# Sheet1.net
KiCad netlist of a schematic drawn in Altium Designer
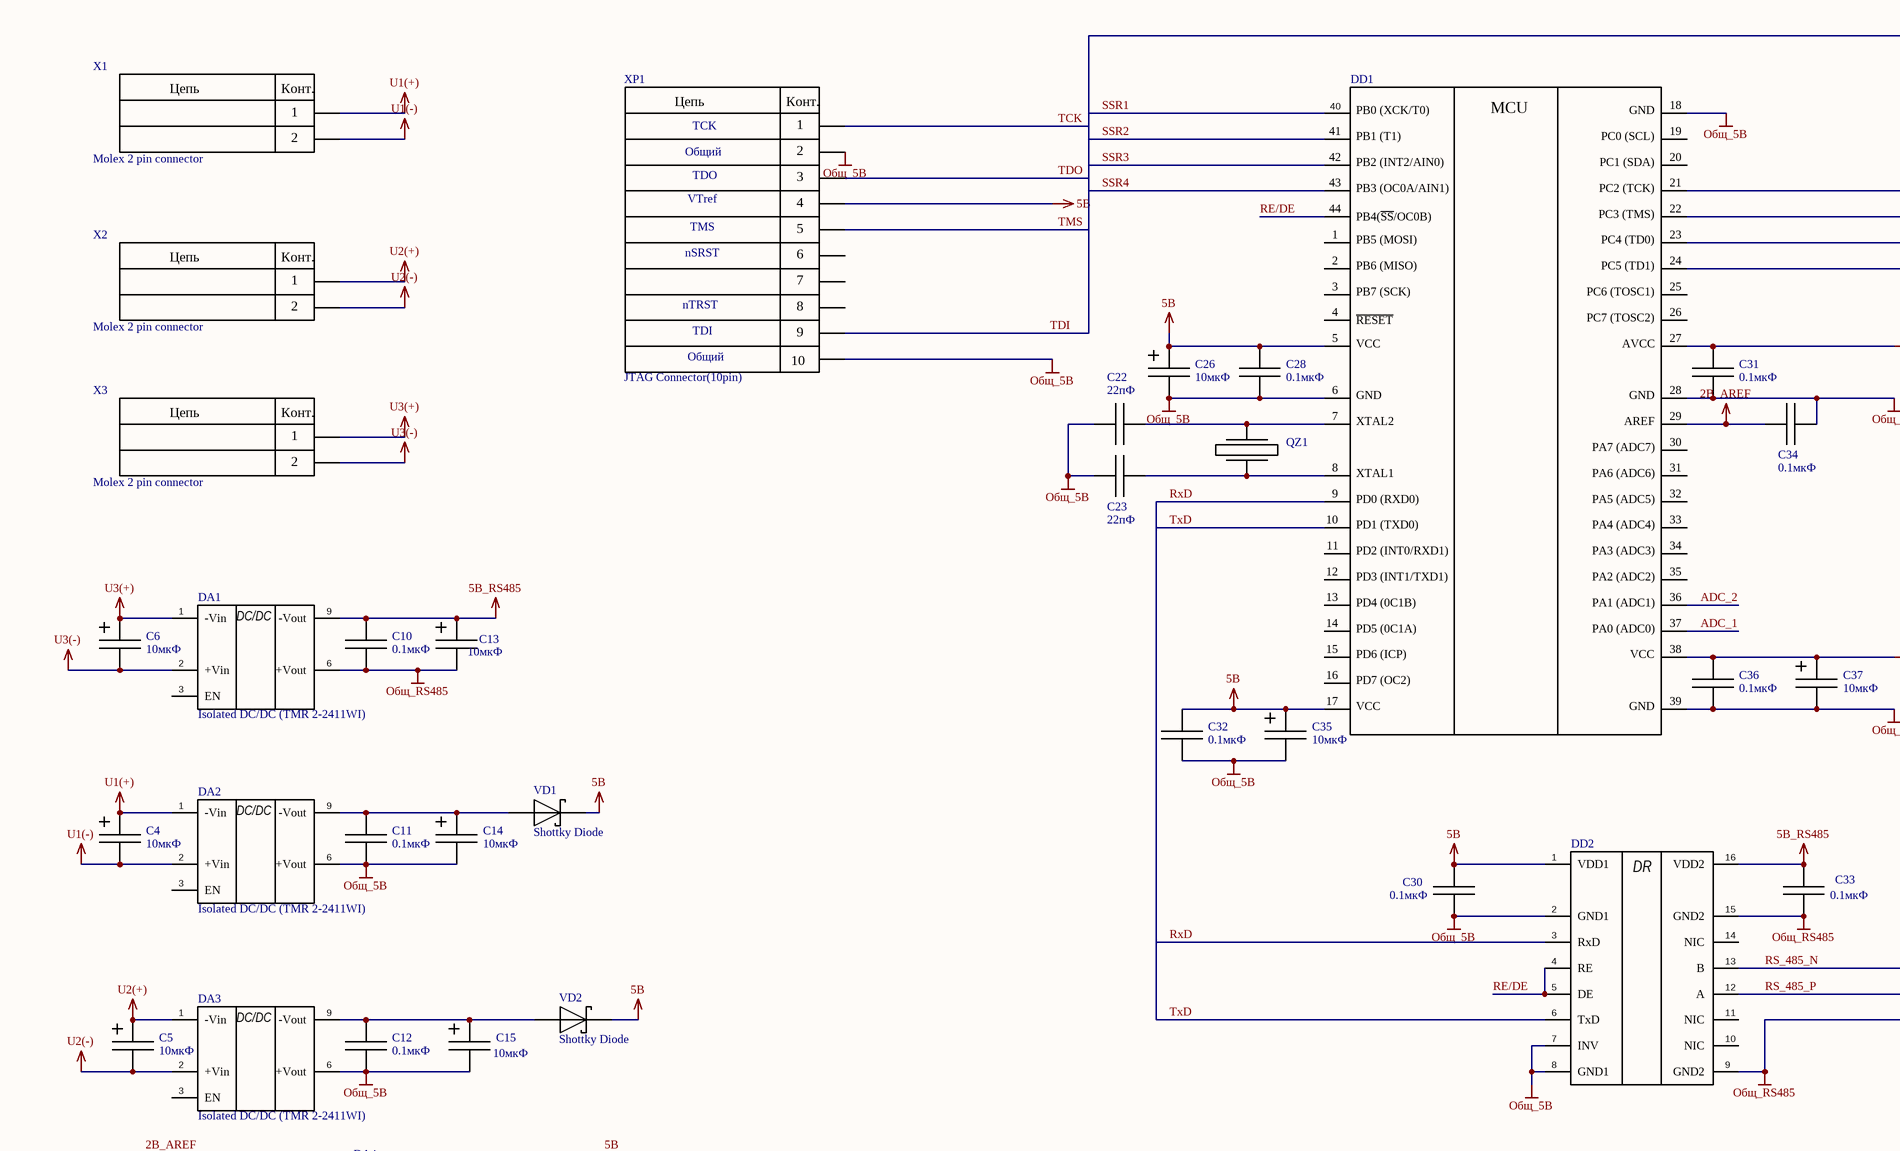
[diagram p0: Sheet1.SchDoc, top left]
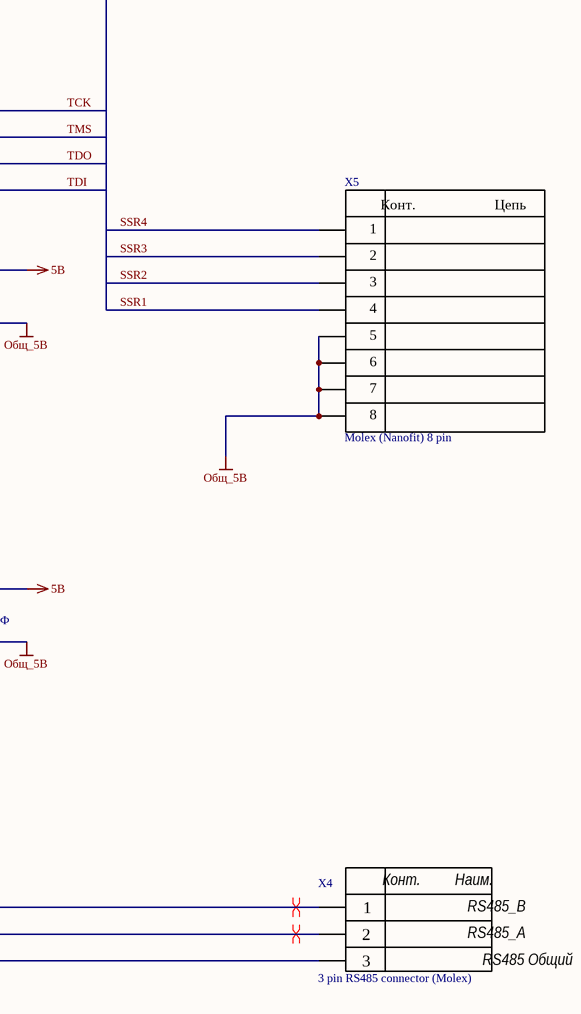
[diagram p1: Sheet1.SchDoc, top right]
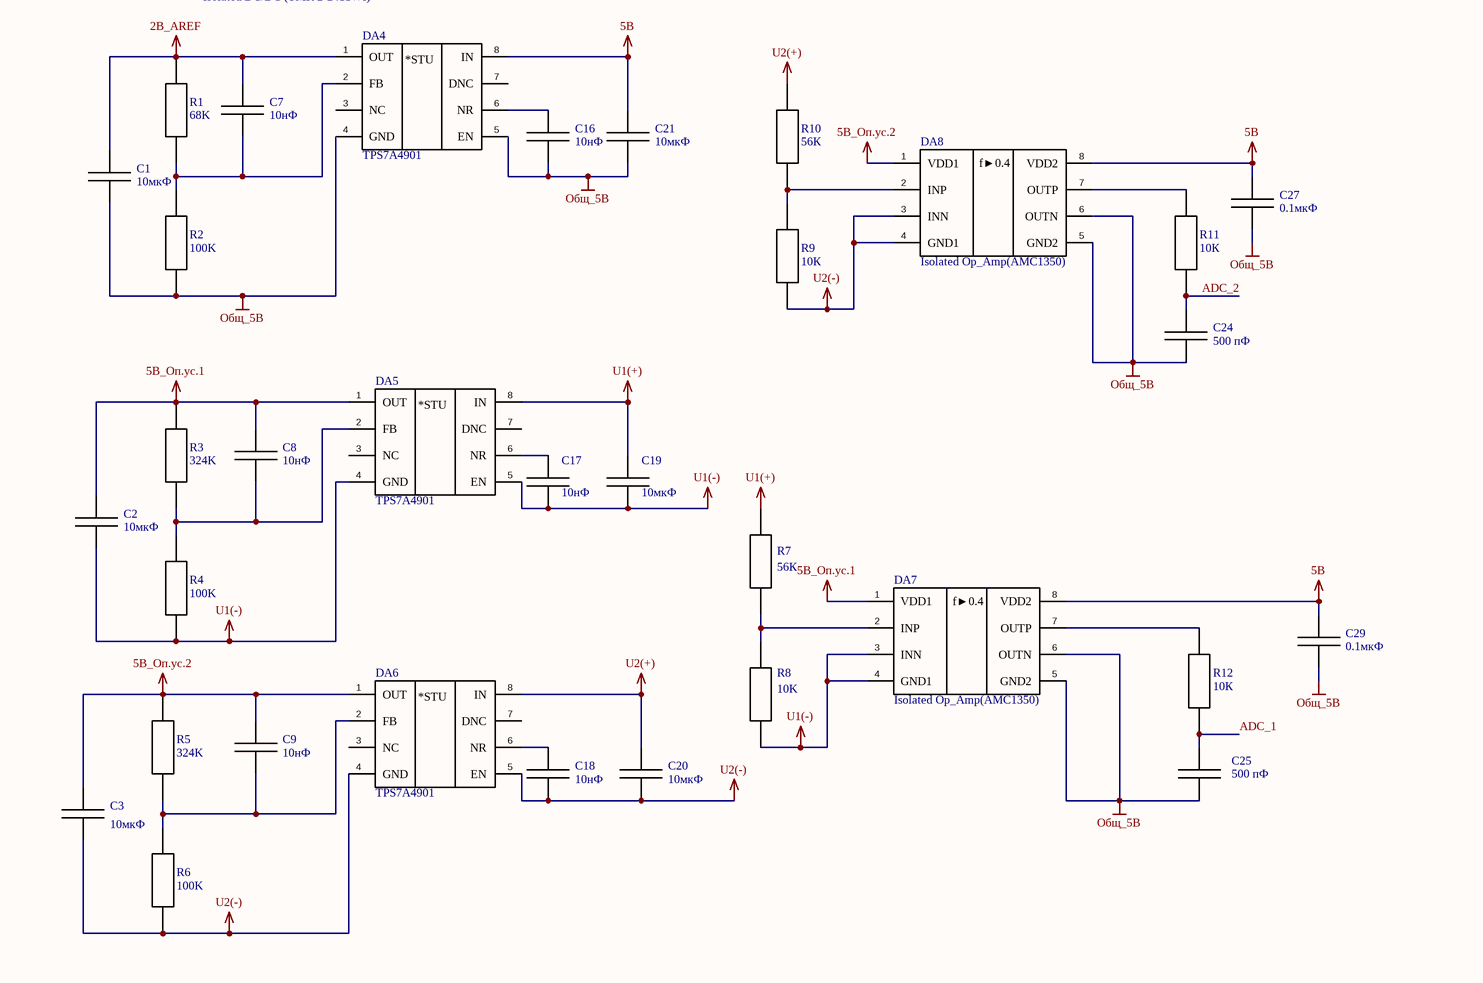
[diagram p2: Sheet1.SchDoc, bottom left]

(export (version "E")
  (design (tool "Eeschema 10.0.6"))
  (components
    (comp (ref "C1") (value "CAP") (footprint "0805") (libsource (lib "Kursovoi proekt") (part "CAP")))
    (comp (ref "C2") (value "CAP") (footprint "0805") (libsource (lib "Kursovoi proekt") (part "CAP")))
    (comp (ref "C3") (value "CAP") (footprint "0805") (libsource (lib "Kursovoi proekt") (part "CAP")))
    (comp (ref "C4")
      (value "CAP")
      (footprint "Cap pol 4x5.4")
      (description "ECAP SMD,  16VV, 105°C")
      (libsource (lib "Kursovoi proekt") (part "Cap Pol 10uF 16V"))
    )
    (comp (ref "C5")
      (value "CAP")
      (footprint "Cap pol 4x5.4")
      (description "ECAP SMD,  16VV, 105°C")
      (libsource (lib "Kursovoi proekt") (part "Cap Pol 10uF 16V"))
    )
    (comp (ref "C6")
      (value "CAP")
      (footprint "Cap pol 4x5.4")
      (description "ECAP SMD,  16VV, 105°C")
      (libsource (lib "Kursovoi proekt") (part "Cap Pol 10uF 16V"))
    )
    (comp (ref "C7") (value "CAP") (footprint "0805") (libsource (lib "Kursovoi proekt") (part "CAP")))
    (comp (ref "C8") (value "CAP") (footprint "0805") (libsource (lib "Kursovoi proekt") (part "CAP")))
    (comp (ref "C9") (value "CAP") (footprint "0805") (libsource (lib "Kursovoi proekt") (part "CAP")))
    (comp (ref "C10") (value "CAP") (footprint "0805") (libsource (lib "Kursovoi proekt") (part "CAP")))
    (comp (ref "C11") (value "CAP") (footprint "0805") (libsource (lib "Kursovoi proekt") (part "CAP")))
    (comp (ref "C12") (value "CAP") (footprint "0805") (libsource (lib "Kursovoi proekt") (part "CAP")))
    (comp (ref "C13")
      (value "CAP")
      (footprint "Cap pol 4x5.4")
      (description "ECAP SMD,  16VV, 105°C")
      (libsource (lib "Kursovoi proekt") (part "Cap Pol 10uF 16V"))
    )
    (comp (ref "C14")
      (value "CAP")
      (footprint "Cap pol 4x5.4")
      (description "ECAP SMD,  16VV, 105°C")
      (libsource (lib "Kursovoi proekt") (part "Cap Pol 10uF 16V"))
    )
    (comp (ref "C15")
      (value "CAP")
      (footprint "Cap pol 4x5.4")
      (description "ECAP SMD,  16VV, 105°C")
      (libsource (lib "Kursovoi proekt") (part "Cap Pol 10uF 16V"))
    )
    (comp (ref "C16") (value "CAP") (footprint "0805") (libsource (lib "Kursovoi proekt") (part "CAP")))
    (comp (ref "C17") (value "CAP") (footprint "0805") (libsource (lib "Kursovoi proekt") (part "CAP")))
    (comp (ref "C18") (value "CAP") (footprint "0805") (libsource (lib "Kursovoi proekt") (part "CAP")))
    (comp (ref "C19") (value "CAP") (footprint "0805") (libsource (lib "Kursovoi proekt") (part "CAP")))
    (comp (ref "C20") (value "CAP") (footprint "0805") (libsource (lib "Kursovoi proekt") (part "CAP")))
    (comp (ref "C21") (value "CAP") (footprint "0805") (libsource (lib "Kursovoi proekt") (part "CAP")))
    (comp (ref "C22") (value "CAP") (footprint "0805") (libsource (lib "Kursovoi proekt") (part "CAP")))
    (comp (ref "C23") (value "CAP") (footprint "0805") (libsource (lib "Kursovoi proekt") (part "CAP")))
    (comp (ref "C24") (value "CAP") (footprint "0805") (libsource (lib "Kursovoi proekt") (part "CAP")))
    (comp (ref "C25") (value "CAP") (footprint "0805") (libsource (lib "Kursovoi proekt") (part "CAP")))
    (comp (ref "C26")
      (value "CAP")
      (footprint "Cap pol 4x5.4")
      (description "ECAP SMD,  16VV, 105°C")
      (libsource (lib "Kursovoi proekt") (part "Cap Pol 10uF 16V"))
    )
    (comp (ref "C27") (value "CAP") (footprint "0805") (libsource (lib "Kursovoi proekt") (part "CAP")))
    (comp (ref "C28") (value "CAP") (footprint "0805") (libsource (lib "Kursovoi proekt") (part "CAP")))
    (comp (ref "C29") (value "CAP") (footprint "0805") (libsource (lib "Kursovoi proekt") (part "CAP")))
    (comp (ref "C30") (value "CAP") (footprint "0805") (libsource (lib "Kursovoi proekt") (part "CAP")))
    (comp (ref "C31") (value "CAP") (footprint "0805") (libsource (lib "Kursovoi proekt") (part "CAP")))
    (comp (ref "C32") (value "CAP") (footprint "0805") (libsource (lib "Kursovoi proekt") (part "CAP")))
    (comp (ref "C33") (value "CAP") (footprint "0805") (libsource (lib "Kursovoi proekt") (part "CAP")))
    (comp (ref "C34") (value "CAP") (footprint "0805") (libsource (lib "Kursovoi proekt") (part "CAP")))
    (comp (ref "C35")
      (value "CAP")
      (footprint "Cap pol 4x5.4")
      (description "ECAP SMD,  16VV, 105°C")
      (libsource (lib "Kursovoi proekt") (part "Cap Pol 10uF 16V"))
    )
    (comp (ref "C36") (value "CAP") (footprint "0805") (libsource (lib "Kursovoi proekt") (part "CAP")))
    (comp (ref "C37")
      (value "CAP")
      (footprint "Cap pol 4x5.4")
      (description "ECAP SMD,  16VV, 105°C")
      (libsource (lib "Kursovoi proekt") (part "Cap Pol 10uF 16V"))
    )
    (comp (ref "DA1")
      (value "Isolated DC/DC (TMR 2-2411WI)")
      (footprint "SIP-9")
      (libsource (lib "Kursovoi proekt") (part "Isolated DC/DC (TMR 2-2411WI)"))
    )
    (comp (ref "DA2")
      (value "Isolated DC/DC (TMR 2-2411WI)")
      (footprint "SIP-9")
      (libsource (lib "Kursovoi proekt") (part "Isolated DC/DC (TMR 2-2411WI)"))
    )
    (comp (ref "DA3")
      (value "Isolated DC/DC (TMR 2-2411WI)")
      (footprint "SIP-9")
      (libsource (lib "Kursovoi proekt") (part "Isolated DC/DC (TMR 2-2411WI)"))
    )
    (comp (ref "DA4")
      (value "TPS7A4901")
      (footprint "HVSSOP-8")
      (libsource (lib "Kursovoi proekt") (part "LDO(TPS7A4901DGNR)"))
    )
    (comp (ref "DA5")
      (value "TPS7A4901")
      (footprint "HVSSOP-8")
      (libsource (lib "Kursovoi proekt") (part "LDO(TPS7A4901DGNR)"))
    )
    (comp (ref "DA6")
      (value "TPS7A4901")
      (footprint "HVSSOP-8")
      (libsource (lib "Kursovoi proekt") (part "LDO(TPS7A4901DGNR)"))
    )
    (comp (ref "DA7")
      (value "Isolated Op_Amp(AMC1350)")
      (footprint "SOIC-8")
      (libsource (lib "Kursovoi proekt") (part "Isolated Op_Amp(AMC1350)"))
    )
    (comp (ref "DA8")
      (value "Isolated Op_Amp(AMC1350)")
      (footprint "SOIC-8")
      (libsource (lib "Kursovoi proekt") (part "Isolated Op_Amp(AMC1350)"))
    )
    (comp (ref "DD1")
      (value "Atmega164PA")
      (footprint "TQFP-44")
      (libsource (lib "Kursovoi proekt") (part "Atmega164PA"))
    )
    (comp (ref "DD2")
      (value "Isolated RS485 Tranciever(ADM2461E)")
      (footprint "SSOP-16")
      (libsource (lib "Kursovoi proekt") (part "Isolated RS485 Tranciever(ADM2461E)"))
    )
    (comp (ref "QZ1") (value "Quartz rez") (footprint "XTAL") (libsource (lib "Kursovoi proekt") (part "QZ")))
    (comp (ref "R1") (value "68K") (footprint "0805") (libsource (lib "Kursovoi proekt") (part "Res")))
    (comp (ref "R2") (value "100K") (footprint "0805") (libsource (lib "Kursovoi proekt") (part "Res")))
    (comp (ref "R3") (value "324K") (footprint "0805") (libsource (lib "Kursovoi proekt") (part "Res")))
    (comp (ref "R4") (value "100K") (footprint "0805") (libsource (lib "Kursovoi proekt") (part "Res")))
    (comp (ref "R5") (value "324K") (footprint "0805") (libsource (lib "Kursovoi proekt") (part "Res")))
    (comp (ref "R6") (value "100K") (footprint "0805") (libsource (lib "Kursovoi proekt") (part "Res")))
    (comp (ref "R7") (value "56К") (footprint "0805") (libsource (lib "Kursovoi proekt") (part "Res")))
    (comp (ref "R8") (value "10K") (footprint "0805") (libsource (lib "Kursovoi proekt") (part "Res")))
    (comp (ref "R9") (value "10К") (footprint "0805") (libsource (lib "Kursovoi proekt") (part "Res")))
    (comp (ref "R10") (value "56К") (footprint "0805") (libsource (lib "Kursovoi proekt") (part "Res")))
    (comp (ref "R11") (value "10К") (footprint "0805") (libsource (lib "Kursovoi proekt") (part "Res")))
    (comp (ref "R12") (value "10К") (footprint "0805") (libsource (lib "Kursovoi proekt") (part "Res")))
    (comp (ref "VD1")
      (value "Shottky Diode")
      (footprint "SMC")
      (libsource (lib "Kursovoi proekt") (part "Shottky Diode"))
    )
    (comp (ref "VD2")
      (value "Shottky Diode")
      (footprint "SMC")
      (libsource (lib "Kursovoi proekt") (part "Shottky Diode"))
    )
    (comp (ref "X1")
      (value "Molex 2 pin connector")
      (footprint "MolexMicroFit 2x1")
      (libsource (lib "Kursovoi proekt") (part "Molex 2 pin connector"))
    )
    (comp (ref "X2")
      (value "Molex 2 pin connector")
      (footprint "MolexMicroFit 2x1")
      (libsource (lib "Kursovoi proekt") (part "Molex 2 pin connector"))
    )
    (comp (ref "X3")
      (value "Molex 2 pin connector")
      (footprint "MolexMicroFit 2x1")
      (libsource (lib "Kursovoi proekt") (part "Molex 2 pin connector"))
    )
    (comp (ref "X4")
      (value "3 pin RS485 connector (Molex)")
      (footprint "MolexMicroFit 3x1")
      (libsource (lib "Kursovoi proekt") (part "3 pin RS485 connector (Molex)"))
    )
    (comp (ref "X5")
      (value "Molex (Nanofit) 8 pin")
      (footprint "Molex Nanofit 8 pin")
      (libsource (lib "Kursovoi proekt") (part "Molex (Nanofit) 8 pin"))
    )
    (comp (ref "XP1")
      (value "JTAG Connector(10pin)")
      (footprint "PLD 10")
      (libsource (lib "Kursovoi proekt") (part "JTAG Connector(10pin)"))
    )
  )
  (nets
    (net (code "1") (name "/ADC_1") (class "Default")
      (node (ref "C25") (pin "1") (pinfunction "1_1") (pintype "passive"))
      (node (ref "DD1") (pin "37") (pinfunction "37_37") (pintype "passive"))
      (node (ref "R12") (pin "1") (pinfunction "1_1") (pintype "passive"))
    )
    (net (code "2") (name "/ADC_2") (class "Default")
      (node (ref "C24") (pin "1") (pinfunction "1_1") (pintype "passive"))
      (node (ref "DD1") (pin "36") (pinfunction "36_36") (pintype "passive"))
      (node (ref "R11") (pin "1") (pinfunction "1_1") (pintype "passive"))
    )
    (net (code "3") (name "/RE{slash}DE") (class "Default")
      (node (ref "DD1") (pin "44") (pinfunction "PB4(~{SS}/OC0B)_44") (pintype "passive"))
      (node (ref "DD2") (pin "4") (pinfunction "RE_4") (pintype "passive"))
      (node (ref "DD2") (pin "5") (pinfunction "DE_5") (pintype "passive"))
    )
    (net (code "4") (name "/RS_485_N") (class "Default")
      (node (ref "DD2") (pin "13") (pinfunction "B_13") (pintype "passive"))
      (node (ref "X4") (pin "1") (pinfunction "1_1") (pintype "passive"))
    )
    (net (code "5") (name "/RS_485_P") (class "Default")
      (node (ref "DD2") (pin "12") (pinfunction "A_12") (pintype "passive"))
      (node (ref "X4") (pin "2") (pinfunction "2_2") (pintype "passive"))
    )
    (net (code "6") (name "/RxD") (class "Default")
      (node (ref "DD1") (pin "9") (pinfunction "9_9") (pintype "passive"))
      (node (ref "DD2") (pin "3") (pinfunction "RxD_3") (pintype "passive"))
    )
    (net (code "7") (name "/SSR1") (class "Default")
      (node (ref "DD1") (pin "40") (pinfunction "40_40") (pintype "passive"))
      (node (ref "X5") (pin "4") (pinfunction "4_4") (pintype "passive"))
    )
    (net (code "8") (name "/SSR2") (class "Default")
      (node (ref "DD1") (pin "41") (pinfunction "41_41") (pintype "passive"))
      (node (ref "X5") (pin "3") (pinfunction "3_3") (pintype "passive"))
    )
    (net (code "9") (name "/SSR3") (class "Default")
      (node (ref "DD1") (pin "42") (pinfunction "42_42") (pintype "passive"))
      (node (ref "X5") (pin "2") (pinfunction "2_2") (pintype "passive"))
    )
    (net (code "10") (name "/SSR4") (class "Default")
      (node (ref "DD1") (pin "43") (pinfunction "43_43") (pintype "passive"))
      (node (ref "X5") (pin "1") (pinfunction "1_1") (pintype "passive"))
    )
    (net (code "11") (name "/TCK") (class "Default")
      (node (ref "DD1") (pin "21") (pinfunction "21_21") (pintype "passive"))
      (node (ref "XP1") (pin "1") (pinfunction "1_1") (pintype "passive"))
    )
    (net (code "12") (name "/TDI") (class "Default")
      (node (ref "DD1") (pin "24") (pinfunction "24_24") (pintype "passive"))
      (node (ref "XP1") (pin "9") (pinfunction "9_9") (pintype "passive"))
    )
    (net (code "13") (name "/TDO") (class "Default")
      (node (ref "DD1") (pin "23") (pinfunction "23_23") (pintype "passive"))
      (node (ref "XP1") (pin "3") (pinfunction "3_3") (pintype "passive"))
    )
    (net (code "14") (name "/TMS") (class "Default")
      (node (ref "DD1") (pin "22") (pinfunction "22_22") (pintype "passive"))
      (node (ref "XP1") (pin "5") (pinfunction "5_5") (pintype "passive"))
    )
    (net (code "15") (name "/TxD") (class "Default")
      (node (ref "DD1") (pin "10") (pinfunction "10_10") (pintype "passive"))
      (node (ref "DD2") (pin "6") (pinfunction "TxD_6") (pintype "passive"))
    )
    (net (code "16") (name "2B_AREF") (class "Default")
      (node (ref "C1") (pin "1") (pinfunction "1_1") (pintype "passive"))
      (node (ref "C34") (pin "2") (pinfunction "2_2") (pintype "passive"))
      (node (ref "C7") (pin "1") (pinfunction "1_1") (pintype "passive"))
      (node (ref "DA4") (pin "1") (pinfunction "OUT_1") (pintype "passive"))
      (node (ref "DD1") (pin "29") (pinfunction "29_29") (pintype "passive"))
      (node (ref "R1") (pin "2") (pinfunction "2_2") (pintype "passive"))
    )
    (net (code "17") (name "5В") (class "Default")
      (node (ref "C21") (pin "1") (pinfunction "1_1") (pintype "passive"))
      (node (ref "C26") (pin "2") (pinfunction "2_2") (pintype "passive"))
      (node (ref "C27") (pin "1") (pinfunction "1_1") (pintype "passive"))
      (node (ref "C28") (pin "1") (pinfunction "1_1") (pintype "passive"))
      (node (ref "C29") (pin "1") (pinfunction "1_1") (pintype "passive"))
      (node (ref "C30") (pin "1") (pinfunction "1_1") (pintype "passive"))
      (node (ref "C31") (pin "1") (pinfunction "1_1") (pintype "passive"))
      (node (ref "C32") (pin "1") (pinfunction "1_1") (pintype "passive"))
      (node (ref "C35") (pin "2") (pinfunction "2_2") (pintype "passive"))
      (node (ref "C36") (pin "1") (pinfunction "1_1") (pintype "passive"))
      (node (ref "C37") (pin "2") (pinfunction "2_2") (pintype "passive"))
      (node (ref "DA4") (pin "8") (pinfunction "IN_8") (pintype "passive"))
      (node (ref "DA7") (pin "8") (pinfunction "VDD2_8") (pintype "passive"))
      (node (ref "DA8") (pin "8") (pinfunction "VDD2_8") (pintype "passive"))
      (node (ref "DD1") (pin "17") (pinfunction "17_17") (pintype "passive"))
      (node (ref "DD1") (pin "27") (pinfunction "27_27") (pintype "passive"))
      (node (ref "DD1") (pin "38") (pinfunction "38_38") (pintype "passive"))
      (node (ref "DD1") (pin "5") (pinfunction "5_5") (pintype "passive"))
      (node (ref "DD2") (pin "1") (pinfunction "VDD1_1") (pintype "passive"))
      (node (ref "VD1") (pin "2") (pinfunction "2_2") (pintype "passive"))
      (node (ref "VD2") (pin "2") (pinfunction "2_2") (pintype "passive"))
      (node (ref "XP1") (pin "4") (pinfunction "4_4") (pintype "passive"))
    )
    (net (code "18") (name "5В_RS485") (class "Default")
      (node (ref "C10") (pin "1") (pinfunction "1_1") (pintype "passive"))
      (node (ref "C13") (pin "2") (pinfunction "2_2") (pintype "passive"))
      (node (ref "C33") (pin "1") (pinfunction "1_1") (pintype "passive"))
      (node (ref "DA1") (pin "9") (pinfunction "-Vout_9") (pintype "passive"))
      (node (ref "DD2") (pin "16") (pinfunction "VDD2_16") (pintype "passive"))
    )
    (net (code "19") (name "5В_Оп.ус.1") (class "Default")
      (node (ref "C2") (pin "1") (pinfunction "1_1") (pintype "passive"))
      (node (ref "C8") (pin "1") (pinfunction "1_1") (pintype "passive"))
      (node (ref "DA5") (pin "1") (pinfunction "OUT_1") (pintype "passive"))
      (node (ref "DA7") (pin "1") (pinfunction "VDD1_1") (pintype "passive"))
      (node (ref "R3") (pin "2") (pinfunction "2_2") (pintype "passive"))
    )
    (net (code "20") (name "5В_Оп.ус.2") (class "Default")
      (node (ref "C3") (pin "1") (pinfunction "1_1") (pintype "passive"))
      (node (ref "C9") (pin "1") (pinfunction "1_1") (pintype "passive"))
      (node (ref "DA6") (pin "1") (pinfunction "OUT_1") (pintype "passive"))
      (node (ref "DA8") (pin "1") (pinfunction "VDD1_1") (pintype "passive"))
      (node (ref "R5") (pin "2") (pinfunction "2_2") (pintype "passive"))
    )
    (net (code "21") (name "Net-(C22-Pad2)") (class "Default")
      (node (ref "C22") (pin "2") (pinfunction "2_2") (pintype "passive"))
      (node (ref "DD1") (pin "7") (pinfunction "7_7") (pintype "passive"))
      (node (ref "QZ1") (pin "2") (pinfunction "2_2") (pintype "passive"))
    )
    (net (code "22") (name "Net-(C23-Pad2)") (class "Default")
      (node (ref "C23") (pin "2") (pinfunction "2_2") (pintype "passive"))
      (node (ref "DD1") (pin "8") (pinfunction "8_8") (pintype "passive"))
      (node (ref "QZ1") (pin "1") (pinfunction "1_1") (pintype "passive"))
    )
    (net (code "23") (name "Net-(DA2--Vout)") (class "Default")
      (node (ref "C11") (pin "1") (pinfunction "1_1") (pintype "passive"))
      (node (ref "C14") (pin "2") (pinfunction "2_2") (pintype "passive"))
      (node (ref "DA2") (pin "9") (pinfunction "-Vout_9") (pintype "passive"))
      (node (ref "VD1") (pin "1") (pinfunction "1_1") (pintype "passive"))
    )
    (net (code "24") (name "Net-(DA3--Vout)") (class "Default")
      (node (ref "C12") (pin "1") (pinfunction "1_1") (pintype "passive"))
      (node (ref "C15") (pin "2") (pinfunction "2_2") (pintype "passive"))
      (node (ref "DA3") (pin "9") (pinfunction "-Vout_9") (pintype "passive"))
      (node (ref "VD2") (pin "1") (pinfunction "1_1") (pintype "passive"))
    )
    (net (code "25") (name "Net-(DA4-FB)") (class "Default")
      (node (ref "C7") (pin "2") (pinfunction "2_2") (pintype "passive"))
      (node (ref "DA4") (pin "2") (pinfunction "FB_2") (pintype "passive"))
      (node (ref "R1") (pin "1") (pinfunction "1_1") (pintype "passive"))
      (node (ref "R2") (pin "2") (pinfunction "2_2") (pintype "passive"))
    )
    (net (code "26") (name "Net-(DA4-NR)") (class "Default")
      (node (ref "C16") (pin "1") (pinfunction "1_1") (pintype "passive"))
      (node (ref "DA4") (pin "6") (pinfunction "NR_6") (pintype "passive"))
    )
    (net (code "27") (name "Net-(DA5-FB)") (class "Default")
      (node (ref "C8") (pin "2") (pinfunction "2_2") (pintype "passive"))
      (node (ref "DA5") (pin "2") (pinfunction "FB_2") (pintype "passive"))
      (node (ref "R3") (pin "1") (pinfunction "1_1") (pintype "passive"))
      (node (ref "R4") (pin "2") (pinfunction "2_2") (pintype "passive"))
    )
    (net (code "28") (name "Net-(DA5-NR)") (class "Default")
      (node (ref "C17") (pin "1") (pinfunction "1_1") (pintype "passive"))
      (node (ref "DA5") (pin "6") (pinfunction "NR_6") (pintype "passive"))
    )
    (net (code "29") (name "Net-(DA6-FB)") (class "Default")
      (node (ref "C9") (pin "2") (pinfunction "2_2") (pintype "passive"))
      (node (ref "DA6") (pin "2") (pinfunction "FB_2") (pintype "passive"))
      (node (ref "R5") (pin "1") (pinfunction "1_1") (pintype "passive"))
      (node (ref "R6") (pin "2") (pinfunction "2_2") (pintype "passive"))
    )
    (net (code "30") (name "Net-(DA6-NR)") (class "Default")
      (node (ref "C18") (pin "1") (pinfunction "1_1") (pintype "passive"))
      (node (ref "DA6") (pin "6") (pinfunction "NR_6") (pintype "passive"))
    )
    (net (code "31") (name "Net-(DA7-INP)") (class "Default")
      (node (ref "DA7") (pin "2") (pinfunction "INP_2") (pintype "passive"))
      (node (ref "R7") (pin "1") (pinfunction "1_1") (pintype "passive"))
      (node (ref "R8") (pin "2") (pinfunction "2_2") (pintype "passive"))
    )
    (net (code "32") (name "Net-(DA7-OUTP)") (class "Default")
      (node (ref "DA7") (pin "7") (pinfunction "OUTP_7") (pintype "passive"))
      (node (ref "R12") (pin "2") (pinfunction "2_2") (pintype "passive"))
    )
    (net (code "33") (name "Net-(DA8-INP)") (class "Default")
      (node (ref "DA8") (pin "2") (pinfunction "INP_2") (pintype "passive"))
      (node (ref "R10") (pin "1") (pinfunction "1_1") (pintype "passive"))
      (node (ref "R9") (pin "2") (pinfunction "2_2") (pintype "passive"))
    )
    (net (code "34") (name "Net-(DA8-OUTP)") (class "Default")
      (node (ref "DA8") (pin "7") (pinfunction "OUTP_7") (pintype "passive"))
      (node (ref "R11") (pin "2") (pinfunction "2_2") (pintype "passive"))
    )
    (net (code "35") (name "U1(+)") (class "Default")
      (node (ref "C19") (pin "1") (pinfunction "1_1") (pintype "passive"))
      (node (ref "C4") (pin "2") (pinfunction "2_2") (pintype "passive"))
      (node (ref "DA2") (pin "1") (pinfunction "-Vin_1") (pintype "passive"))
      (node (ref "DA5") (pin "8") (pinfunction "IN_8") (pintype "passive"))
      (node (ref "R7") (pin "2") (pinfunction "2_2") (pintype "passive"))
      (node (ref "X1") (pin "1") (pinfunction "1_1") (pintype "passive"))
    )
    (net (code "36") (name "U1(-)") (class "Default")
      (node (ref "C17") (pin "2") (pinfunction "2_2") (pintype "passive"))
      (node (ref "C19") (pin "2") (pinfunction "2_2") (pintype "passive"))
      (node (ref "C2") (pin "2") (pinfunction "2_2") (pintype "passive"))
      (node (ref "C4") (pin "1") (pinfunction "1_1") (pintype "passive"))
      (node (ref "DA2") (pin "2") (pinfunction "+Vin_2") (pintype "passive"))
      (node (ref "DA5") (pin "4") (pinfunction "GND_4") (pintype "passive"))
      (node (ref "DA5") (pin "5") (pinfunction "EN_5") (pintype "passive"))
      (node (ref "DA7") (pin "3") (pinfunction "INN_3") (pintype "passive"))
      (node (ref "DA7") (pin "4") (pinfunction "GND1_4") (pintype "passive"))
      (node (ref "R4") (pin "1") (pinfunction "1_1") (pintype "passive"))
      (node (ref "R8") (pin "1") (pinfunction "1_1") (pintype "passive"))
      (node (ref "X1") (pin "2") (pinfunction "2_2") (pintype "passive"))
    )
    (net (code "37") (name "U2(+)") (class "Default")
      (node (ref "C20") (pin "1") (pinfunction "1_1") (pintype "passive"))
      (node (ref "C5") (pin "2") (pinfunction "2_2") (pintype "passive"))
      (node (ref "DA3") (pin "1") (pinfunction "-Vin_1") (pintype "passive"))
      (node (ref "DA6") (pin "8") (pinfunction "IN_8") (pintype "passive"))
      (node (ref "R10") (pin "2") (pinfunction "2_2") (pintype "passive"))
      (node (ref "X2") (pin "1") (pinfunction "1_1") (pintype "passive"))
    )
    (net (code "38") (name "U2(-)") (class "Default")
      (node (ref "C18") (pin "2") (pinfunction "2_2") (pintype "passive"))
      (node (ref "C20") (pin "2") (pinfunction "2_2") (pintype "passive"))
      (node (ref "C3") (pin "2") (pinfunction "2_2") (pintype "passive"))
      (node (ref "C5") (pin "1") (pinfunction "1_1") (pintype "passive"))
      (node (ref "DA3") (pin "2") (pinfunction "+Vin_2") (pintype "passive"))
      (node (ref "DA6") (pin "4") (pinfunction "GND_4") (pintype "passive"))
      (node (ref "DA6") (pin "5") (pinfunction "EN_5") (pintype "passive"))
      (node (ref "DA8") (pin "3") (pinfunction "INN_3") (pintype "passive"))
      (node (ref "DA8") (pin "4") (pinfunction "GND1_4") (pintype "passive"))
      (node (ref "R6") (pin "1") (pinfunction "1_1") (pintype "passive"))
      (node (ref "R9") (pin "1") (pinfunction "1_1") (pintype "passive"))
      (node (ref "X2") (pin "2") (pinfunction "2_2") (pintype "passive"))
    )
    (net (code "39") (name "U3(+)") (class "Default")
      (node (ref "C6") (pin "2") (pinfunction "2_2") (pintype "passive"))
      (node (ref "DA1") (pin "1") (pinfunction "-Vin_1") (pintype "passive"))
      (node (ref "X3") (pin "1") (pinfunction "1_1") (pintype "passive"))
    )
    (net (code "40") (name "U3(-)") (class "Default")
      (node (ref "C6") (pin "1") (pinfunction "1_1") (pintype "passive"))
      (node (ref "DA1") (pin "2") (pinfunction "+Vin_2") (pintype "passive"))
      (node (ref "X3") (pin "2") (pinfunction "2_2") (pintype "passive"))
    )
    (net (code "41") (name "unconnected-(DA1-EN-Pad3)") (class "Default")
      (node (ref "DA1") (pin "3") (pinfunction "EN_3") (pintype "passive"))
    )
    (net (code "42") (name "unconnected-(DA2-EN-Pad3)") (class "Default")
      (node (ref "DA2") (pin "3") (pinfunction "EN_3") (pintype "passive"))
    )
    (net (code "43") (name "unconnected-(DA3-EN-Pad3)") (class "Default")
      (node (ref "DA3") (pin "3") (pinfunction "EN_3") (pintype "passive"))
    )
    (net (code "44") (name "unconnected-(DA4-DNC-Pad7)") (class "Default")
      (node (ref "DA4") (pin "7") (pinfunction "DNC_7") (pintype "passive"))
    )
    (net (code "45") (name "unconnected-(DA4-NC-Pad3)") (class "Default")
      (node (ref "DA4") (pin "3") (pinfunction "NC_3") (pintype "passive"))
    )
    (net (code "46") (name "unconnected-(DA5-DNC-Pad7)") (class "Default")
      (node (ref "DA5") (pin "7") (pinfunction "DNC_7") (pintype "passive"))
    )
    (net (code "47") (name "unconnected-(DA5-NC-Pad3)") (class "Default")
      (node (ref "DA5") (pin "3") (pinfunction "NC_3") (pintype "passive"))
    )
    (net (code "48") (name "unconnected-(DA6-DNC-Pad7)") (class "Default")
      (node (ref "DA6") (pin "7") (pinfunction "DNC_7") (pintype "passive"))
    )
    (net (code "49") (name "unconnected-(DA6-NC-Pad3)") (class "Default")
      (node (ref "DA6") (pin "3") (pinfunction "NC_3") (pintype "passive"))
    )
    (net (code "50") (name "unconnected-(DD1-Pad1)") (class "Default")
      (node (ref "DD1") (pin "1") (pinfunction "1_1") (pintype "passive"))
    )
    (net (code "51") (name "unconnected-(DD1-Pad2)") (class "Default")
      (node (ref "DD1") (pin "2") (pinfunction "2_2") (pintype "passive"))
    )
    (net (code "52") (name "unconnected-(DD1-Pad3)") (class "Default")
      (node (ref "DD1") (pin "3") (pinfunction "3_3") (pintype "passive"))
    )
    (net (code "53") (name "unconnected-(DD1-Pad11)") (class "Default")
      (node (ref "DD1") (pin "11") (pinfunction "11_11") (pintype "passive"))
    )
    (net (code "54") (name "unconnected-(DD1-Pad12)") (class "Default")
      (node (ref "DD1") (pin "12") (pinfunction "12_12") (pintype "passive"))
    )
    (net (code "55") (name "unconnected-(DD1-Pad13)") (class "Default")
      (node (ref "DD1") (pin "13") (pinfunction "13_13") (pintype "passive"))
    )
    (net (code "56") (name "unconnected-(DD1-Pad14)") (class "Default")
      (node (ref "DD1") (pin "14") (pinfunction "14_14") (pintype "passive"))
    )
    (net (code "57") (name "unconnected-(DD1-Pad15)") (class "Default")
      (node (ref "DD1") (pin "15") (pinfunction "15_15") (pintype "passive"))
    )
    (net (code "58") (name "unconnected-(DD1-Pad16)") (class "Default")
      (node (ref "DD1") (pin "16") (pinfunction "16_16") (pintype "passive"))
    )
    (net (code "59") (name "unconnected-(DD1-Pad19)") (class "Default")
      (node (ref "DD1") (pin "19") (pinfunction "19_19") (pintype "passive"))
    )
    (net (code "60") (name "unconnected-(DD1-Pad20)") (class "Default")
      (node (ref "DD1") (pin "20") (pinfunction "20_20") (pintype "passive"))
    )
    (net (code "61") (name "unconnected-(DD1-Pad25)") (class "Default")
      (node (ref "DD1") (pin "25") (pinfunction "25_25") (pintype "passive"))
    )
    (net (code "62") (name "unconnected-(DD1-Pad26)") (class "Default")
      (node (ref "DD1") (pin "26") (pinfunction "26_26") (pintype "passive"))
    )
    (net (code "63") (name "unconnected-(DD1-Pad30)") (class "Default")
      (node (ref "DD1") (pin "30") (pinfunction "30_30") (pintype "passive"))
    )
    (net (code "64") (name "unconnected-(DD1-Pad31)") (class "Default")
      (node (ref "DD1") (pin "31") (pinfunction "31_31") (pintype "passive"))
    )
    (net (code "65") (name "unconnected-(DD1-Pad32)") (class "Default")
      (node (ref "DD1") (pin "32") (pinfunction "32_32") (pintype "passive"))
    )
    (net (code "66") (name "unconnected-(DD1-Pad33)") (class "Default")
      (node (ref "DD1") (pin "33") (pinfunction "33_33") (pintype "passive"))
    )
    (net (code "67") (name "unconnected-(DD1-Pad34)") (class "Default")
      (node (ref "DD1") (pin "34") (pinfunction "34_34") (pintype "passive"))
    )
    (net (code "68") (name "unconnected-(DD1-Pad35)") (class "Default")
      (node (ref "DD1") (pin "35") (pinfunction "35_35") (pintype "passive"))
    )
    (net (code "69") (name "unconnected-(DD1-~{RESET}-Pad4)") (class "Default")
      (node (ref "DD1") (pin "4") (pinfunction "~{RESET}_4") (pintype "passive"))
    )
    (net (code "70") (name "unconnected-(DD2-NIC-Pad10)") (class "Default")
      (node (ref "DD2") (pin "10") (pinfunction "NIC_10") (pintype "passive"))
    )
    (net (code "71") (name "unconnected-(DD2-NIC-Pad11)") (class "Default")
      (node (ref "DD2") (pin "11") (pinfunction "NIC_11") (pintype "passive"))
    )
    (net (code "72") (name "unconnected-(DD2-NIC-Pad14)") (class "Default")
      (node (ref "DD2") (pin "14") (pinfunction "NIC_14") (pintype "passive"))
    )
    (net (code "73") (name "unconnected-(XP1-Pad6)") (class "Default")
      (node (ref "XP1") (pin "6") (pinfunction "6_6") (pintype "passive"))
    )
    (net (code "74") (name "unconnected-(XP1-Pad7)") (class "Default")
      (node (ref "XP1") (pin "7") (pinfunction "7_7") (pintype "passive"))
    )
    (net (code "75") (name "unconnected-(XP1-Pad8)") (class "Default")
      (node (ref "XP1") (pin "8") (pinfunction "8_8") (pintype "passive"))
    )
    (net (code "76") (name "Общ_5В") (class "Default")
      (node (ref "C1") (pin "2") (pinfunction "2_2") (pintype "passive"))
      (node (ref "C11") (pin "2") (pinfunction "2_2") (pintype "passive"))
      (node (ref "C12") (pin "2") (pinfunction "2_2") (pintype "passive"))
      (node (ref "C14") (pin "1") (pinfunction "1_1") (pintype "passive"))
      (node (ref "C15") (pin "1") (pinfunction "1_1") (pintype "passive"))
      (node (ref "C16") (pin "2") (pinfunction "2_2") (pintype "passive"))
      (node (ref "C21") (pin "2") (pinfunction "2_2") (pintype "passive"))
      (node (ref "C22") (pin "1") (pinfunction "1_1") (pintype "passive"))
      (node (ref "C23") (pin "1") (pinfunction "1_1") (pintype "passive"))
      (node (ref "C24") (pin "2") (pinfunction "2_2") (pintype "passive"))
      (node (ref "C25") (pin "2") (pinfunction "2_2") (pintype "passive"))
      (node (ref "C26") (pin "1") (pinfunction "1_1") (pintype "passive"))
      (node (ref "C27") (pin "2") (pinfunction "2_2") (pintype "passive"))
      (node (ref "C28") (pin "2") (pinfunction "2_2") (pintype "passive"))
      (node (ref "C29") (pin "2") (pinfunction "2_2") (pintype "passive"))
      (node (ref "C30") (pin "2") (pinfunction "2_2") (pintype "passive"))
      (node (ref "C31") (pin "2") (pinfunction "2_2") (pintype "passive"))
      (node (ref "C32") (pin "2") (pinfunction "2_2") (pintype "passive"))
      (node (ref "C34") (pin "1") (pinfunction "1_1") (pintype "passive"))
      (node (ref "C35") (pin "1") (pinfunction "1_1") (pintype "passive"))
      (node (ref "C36") (pin "2") (pinfunction "2_2") (pintype "passive"))
      (node (ref "C37") (pin "1") (pinfunction "1_1") (pintype "passive"))
      (node (ref "DA2") (pin "6") (pinfunction "+Vout_6") (pintype "passive"))
      (node (ref "DA3") (pin "6") (pinfunction "+Vout_6") (pintype "passive"))
      (node (ref "DA4") (pin "4") (pinfunction "GND_4") (pintype "passive"))
      (node (ref "DA4") (pin "5") (pinfunction "EN_5") (pintype "passive"))
      (node (ref "DA7") (pin "5") (pinfunction "GND2_5") (pintype "passive"))
      (node (ref "DA7") (pin "6") (pinfunction "OUTN_6") (pintype "passive"))
      (node (ref "DA8") (pin "5") (pinfunction "GND2_5") (pintype "passive"))
      (node (ref "DA8") (pin "6") (pinfunction "OUTN_6") (pintype "passive"))
      (node (ref "DD1") (pin "18") (pinfunction "18_18") (pintype "passive"))
      (node (ref "DD1") (pin "28") (pinfunction "28_28") (pintype "passive"))
      (node (ref "DD1") (pin "39") (pinfunction "39_39") (pintype "passive"))
      (node (ref "DD1") (pin "6") (pinfunction "6_6") (pintype "passive"))
      (node (ref "DD2") (pin "2") (pinfunction "GND1_2") (pintype "passive"))
      (node (ref "DD2") (pin "7") (pinfunction "INV_7") (pintype "passive"))
      (node (ref "DD2") (pin "8") (pinfunction "GND1_8") (pintype "passive"))
      (node (ref "R2") (pin "1") (pinfunction "1_1") (pintype "passive"))
      (node (ref "X5") (pin "5") (pinfunction "5_5") (pintype "passive"))
      (node (ref "X5") (pin "6") (pinfunction "6_6") (pintype "passive"))
      (node (ref "X5") (pin "7") (pinfunction "7_7") (pintype "passive"))
      (node (ref "X5") (pin "8") (pinfunction "8_8") (pintype "passive"))
      (node (ref "XP1") (pin "10") (pinfunction "10_10") (pintype "passive"))
      (node (ref "XP1") (pin "2") (pinfunction "2_2") (pintype "passive"))
    )
    (net (code "77") (name "Общ_RS485") (class "Default")
      (node (ref "C10") (pin "2") (pinfunction "2_2") (pintype "passive"))
      (node (ref "C13") (pin "1") (pinfunction "1_1") (pintype "passive"))
      (node (ref "C33") (pin "2") (pinfunction "2_2") (pintype "passive"))
      (node (ref "DA1") (pin "6") (pinfunction "+Vout_6") (pintype "passive"))
      (node (ref "DD2") (pin "15") (pinfunction "GND2_15") (pintype "passive"))
      (node (ref "DD2") (pin "9") (pinfunction "GND2_9") (pintype "passive"))
      (node (ref "X4") (pin "3") (pinfunction "3_3") (pintype "passive"))
    )
  )
)
